# tappytap.net
KiCad netlist of a schematic drawn in EAGLE
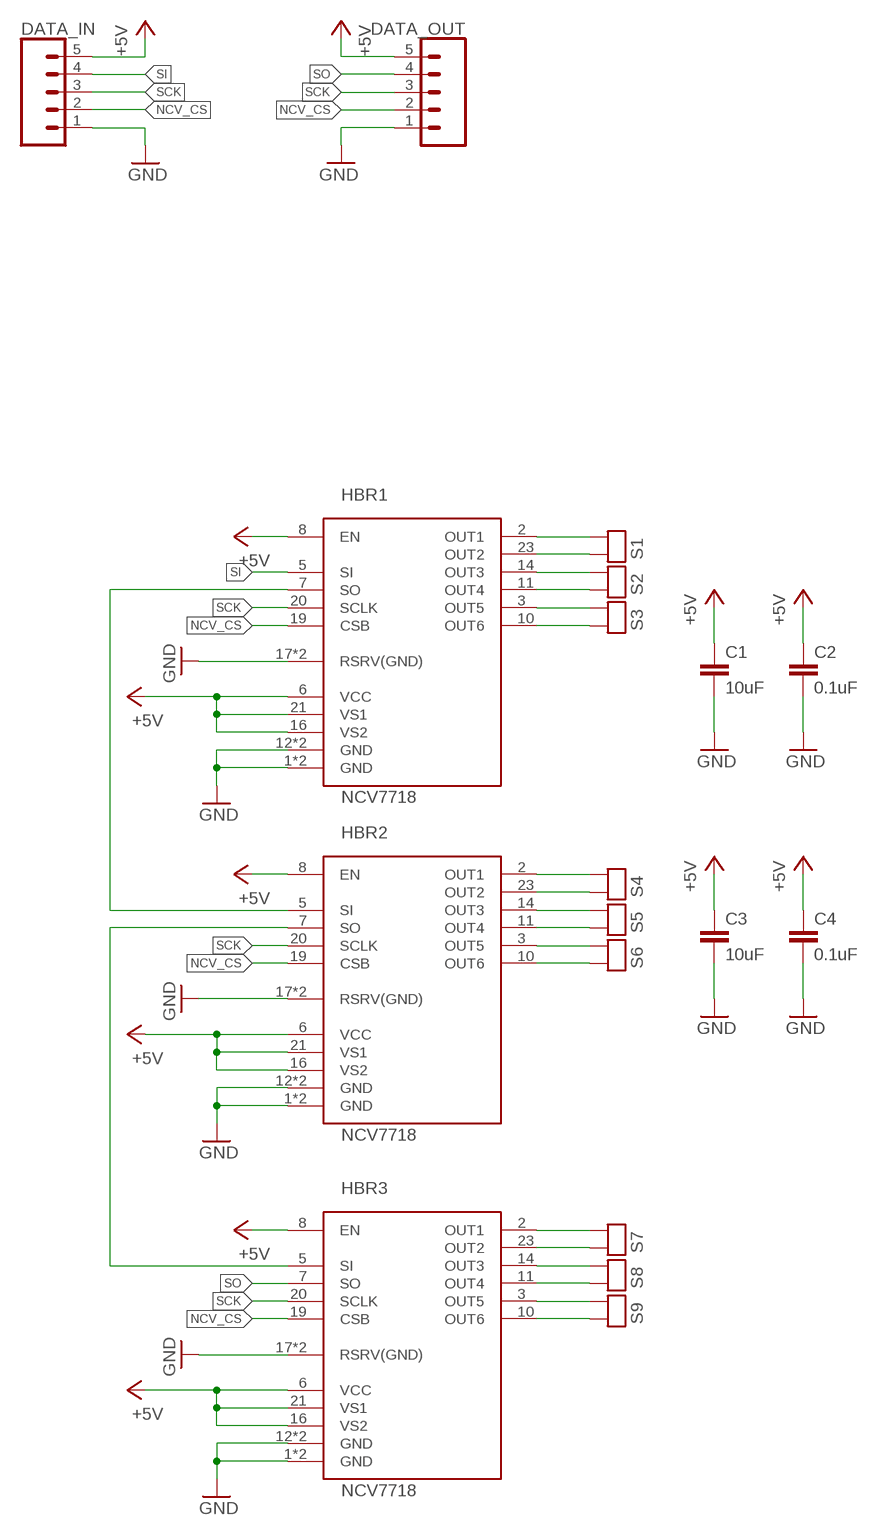
[diagram p0: schematic, sheet 1]

(export (version "E")
  (design (tool "Eeschema 10.0.6"))
  (components
    (comp (ref "C1")
      (value "10uF")
      (footprint "eagle-import:C0603")
      (libsource (lib "eagle-import") (part "C-EUC0603"))
    )
    (comp (ref "C2")
      (value "0.1uF")
      (footprint "eagle-import:C0603")
      (libsource (lib "eagle-import") (part "C-EUC0603"))
    )
    (comp (ref "C3")
      (value "10uF")
      (footprint "eagle-import:C0603")
      (libsource (lib "eagle-import") (part "C-EUC0603"))
    )
    (comp (ref "C4")
      (value "0.1uF")
      (footprint "eagle-import:C0603")
      (libsource (lib "eagle-import") (part "C-EUC0603"))
    )
    (comp (ref "DATA_IN")
      (value "CONN_05")
      (footprint "eagle-import:1X05")
      (libsource (lib "eagle-import") (part "CONN_05"))
    )
    (comp (ref "DATA_OUT")
      (value "CONN_05")
      (footprint "eagle-import:1X05")
      (libsource (lib "eagle-import") (part "CONN_05"))
    )
    (comp (ref "HBR1")
      (value "NCV7718")
      (footprint "eagle-import:24-SSOP")
      (libsource (lib "eagle-import") (part "NCV7718"))
    )
    (comp (ref "HBR2")
      (value "NCV7718")
      (footprint "eagle-import:24-SSOP")
      (libsource (lib "eagle-import") (part "NCV7718"))
    )
    (comp (ref "HBR3")
      (value "NCV7718")
      (footprint "eagle-import:24-SSOP")
      (libsource (lib "eagle-import") (part "NCV7718"))
    )
    (comp (ref "S1")
      (value "TP2")
      (footprint "eagle-import:TP2_2MM")
      (libsource (lib "eagle-import") (part "TP2"))
    )
    (comp (ref "S2")
      (value "TP2")
      (footprint "eagle-import:TP2_2MM")
      (libsource (lib "eagle-import") (part "TP2"))
    )
    (comp (ref "S3")
      (value "TP2")
      (footprint "eagle-import:TP2_2MM")
      (libsource (lib "eagle-import") (part "TP2"))
    )
    (comp (ref "S4")
      (value "TP2")
      (footprint "eagle-import:TP2_2MM")
      (libsource (lib "eagle-import") (part "TP2"))
    )
    (comp (ref "S5")
      (value "TP2")
      (footprint "eagle-import:TP2_2MM")
      (libsource (lib "eagle-import") (part "TP2"))
    )
    (comp (ref "S6")
      (value "TP2")
      (footprint "eagle-import:TP2_2MM")
      (libsource (lib "eagle-import") (part "TP2"))
    )
    (comp (ref "S7")
      (value "TP2")
      (footprint "eagle-import:TP2_2MM")
      (libsource (lib "eagle-import") (part "TP2"))
    )
    (comp (ref "S8")
      (value "TP2")
      (footprint "eagle-import:TP2_2MM")
      (libsource (lib "eagle-import") (part "TP2"))
    )
    (comp (ref "S9")
      (value "TP2")
      (footprint "eagle-import:TP2_2MM")
      (libsource (lib "eagle-import") (part "TP2"))
    )
  )
  (nets
    (net (code "1") (name "+5V") (class "Default")
      (node (ref "C1") (pin "1") (pinfunction "1_1") (pintype "passive"))
      (node (ref "C2") (pin "1") (pinfunction "1_1") (pintype "passive"))
      (node (ref "C3") (pin "1") (pinfunction "1_1") (pintype "passive"))
      (node (ref "C4") (pin "1") (pinfunction "1_1") (pintype "passive"))
      (node (ref "DATA_IN") (pin "5") (pinfunction "5_5") (pintype "passive"))
      (node (ref "DATA_OUT") (pin "5") (pinfunction "5_5") (pintype "passive"))
      (node (ref "HBR1") (pin "16") (pinfunction "VS2_16") (pintype "bidirectional"))
      (node (ref "HBR1") (pin "21") (pinfunction "VS1_21") (pintype "bidirectional"))
      (node (ref "HBR1") (pin "6") (pinfunction "VCC_6") (pintype "bidirectional"))
      (node (ref "HBR1") (pin "8") (pinfunction "EN_8") (pintype "bidirectional"))
      (node (ref "HBR2") (pin "16") (pinfunction "VS2_16") (pintype "bidirectional"))
      (node (ref "HBR2") (pin "21") (pinfunction "VS1_21") (pintype "bidirectional"))
      (node (ref "HBR2") (pin "6") (pinfunction "VCC_6") (pintype "bidirectional"))
      (node (ref "HBR2") (pin "8") (pinfunction "EN_8") (pintype "bidirectional"))
      (node (ref "HBR3") (pin "16") (pinfunction "VS2_16") (pintype "bidirectional"))
      (node (ref "HBR3") (pin "21") (pinfunction "VS1_21") (pintype "bidirectional"))
      (node (ref "HBR3") (pin "6") (pinfunction "VCC_6") (pintype "bidirectional"))
      (node (ref "HBR3") (pin "8") (pinfunction "EN_8") (pintype "bidirectional"))
    )
    (net (code "2") (name "GND") (class "Default")
      (node (ref "C1") (pin "2") (pinfunction "2_2") (pintype "passive"))
      (node (ref "C2") (pin "2") (pinfunction "2_2") (pintype "passive"))
      (node (ref "C3") (pin "2") (pinfunction "2_2") (pintype "passive"))
      (node (ref "C4") (pin "2") (pinfunction "2_2") (pintype "passive"))
      (node (ref "DATA_IN") (pin "1") (pinfunction "1_1") (pintype "passive"))
      (node (ref "DATA_OUT") (pin "1") (pinfunction "1_1") (pintype "passive"))
      (node (ref "HBR1") (pin "1") (pinfunction "GND_1") (pintype "bidirectional"))
      (node (ref "HBR1") (pin "12") (pinfunction "GND_12") (pintype "bidirectional"))
      (node (ref "HBR1") (pin "13") (pinfunction "GND_13") (pintype "bidirectional"))
      (node (ref "HBR1") (pin "17") (pinfunction "RSRV(GND)_17") (pintype "bidirectional"))
      (node (ref "HBR1") (pin "18") (pinfunction "RSRV(GND)_18") (pintype "bidirectional"))
      (node (ref "HBR1") (pin "24") (pinfunction "GND_24") (pintype "bidirectional"))
      (node (ref "HBR2") (pin "1") (pinfunction "GND_1") (pintype "bidirectional"))
      (node (ref "HBR2") (pin "12") (pinfunction "GND_12") (pintype "bidirectional"))
      (node (ref "HBR2") (pin "13") (pinfunction "GND_13") (pintype "bidirectional"))
      (node (ref "HBR2") (pin "17") (pinfunction "RSRV(GND)_17") (pintype "bidirectional"))
      (node (ref "HBR2") (pin "18") (pinfunction "RSRV(GND)_18") (pintype "bidirectional"))
      (node (ref "HBR2") (pin "24") (pinfunction "GND_24") (pintype "bidirectional"))
      (node (ref "HBR3") (pin "1") (pinfunction "GND_1") (pintype "bidirectional"))
      (node (ref "HBR3") (pin "12") (pinfunction "GND_12") (pintype "bidirectional"))
      (node (ref "HBR3") (pin "13") (pinfunction "GND_13") (pintype "bidirectional"))
      (node (ref "HBR3") (pin "17") (pinfunction "RSRV(GND)_17") (pintype "bidirectional"))
      (node (ref "HBR3") (pin "18") (pinfunction "RSRV(GND)_18") (pintype "bidirectional"))
      (node (ref "HBR3") (pin "24") (pinfunction "GND_24") (pintype "bidirectional"))
    )
    (net (code "3") (name "NCV_CS") (class "Default")
      (node (ref "DATA_IN") (pin "2") (pinfunction "2_2") (pintype "passive"))
      (node (ref "DATA_OUT") (pin "2") (pinfunction "2_2") (pintype "passive"))
      (node (ref "HBR1") (pin "19") (pinfunction "CSB_19") (pintype "bidirectional"))
      (node (ref "HBR2") (pin "19") (pinfunction "CSB_19") (pintype "bidirectional"))
      (node (ref "HBR3") (pin "19") (pinfunction "CSB_19") (pintype "bidirectional"))
    )
    (net (code "4") (name "Net-(HBR1-OUT1)") (class "Default")
      (node (ref "HBR1") (pin "2") (pinfunction "OUT1_2") (pintype "bidirectional"))
      (node (ref "S1") (pin "P$1") (pinfunction "0_P$1") (pintype "bidirectional"))
    )
    (net (code "5") (name "Net-(HBR1-OUT2)") (class "Default")
      (node (ref "HBR1") (pin "23") (pinfunction "OUT2_23") (pintype "bidirectional"))
      (node (ref "S1") (pin "P$2") (pinfunction "1_P$2") (pintype "bidirectional"))
    )
    (net (code "6") (name "Net-(HBR1-OUT3)") (class "Default")
      (node (ref "HBR1") (pin "14") (pinfunction "OUT3_14") (pintype "bidirectional"))
      (node (ref "S2") (pin "P$1") (pinfunction "0_P$1") (pintype "bidirectional"))
    )
    (net (code "7") (name "Net-(HBR1-OUT4)") (class "Default")
      (node (ref "HBR1") (pin "11") (pinfunction "OUT4_11") (pintype "bidirectional"))
      (node (ref "S2") (pin "P$2") (pinfunction "1_P$2") (pintype "bidirectional"))
    )
    (net (code "8") (name "Net-(HBR1-OUT5)") (class "Default")
      (node (ref "HBR1") (pin "3") (pinfunction "OUT5_3") (pintype "bidirectional"))
      (node (ref "S3") (pin "P$1") (pinfunction "0_P$1") (pintype "bidirectional"))
    )
    (net (code "9") (name "Net-(HBR1-OUT6)") (class "Default")
      (node (ref "HBR1") (pin "10") (pinfunction "OUT6_10") (pintype "bidirectional"))
      (node (ref "S3") (pin "P$2") (pinfunction "1_P$2") (pintype "bidirectional"))
    )
    (net (code "10") (name "Net-(HBR1-SO)") (class "Default")
      (node (ref "HBR1") (pin "7") (pinfunction "SO_7") (pintype "bidirectional"))
      (node (ref "HBR2") (pin "5") (pinfunction "SI_5") (pintype "bidirectional"))
    )
    (net (code "11") (name "Net-(HBR2-OUT1)") (class "Default")
      (node (ref "HBR2") (pin "2") (pinfunction "OUT1_2") (pintype "bidirectional"))
      (node (ref "S4") (pin "P$1") (pinfunction "0_P$1") (pintype "bidirectional"))
    )
    (net (code "12") (name "Net-(HBR2-OUT2)") (class "Default")
      (node (ref "HBR2") (pin "23") (pinfunction "OUT2_23") (pintype "bidirectional"))
      (node (ref "S4") (pin "P$2") (pinfunction "1_P$2") (pintype "bidirectional"))
    )
    (net (code "13") (name "Net-(HBR2-OUT3)") (class "Default")
      (node (ref "HBR2") (pin "14") (pinfunction "OUT3_14") (pintype "bidirectional"))
      (node (ref "S5") (pin "P$1") (pinfunction "0_P$1") (pintype "bidirectional"))
    )
    (net (code "14") (name "Net-(HBR2-OUT4)") (class "Default")
      (node (ref "HBR2") (pin "11") (pinfunction "OUT4_11") (pintype "bidirectional"))
      (node (ref "S5") (pin "P$2") (pinfunction "1_P$2") (pintype "bidirectional"))
    )
    (net (code "15") (name "Net-(HBR2-OUT5)") (class "Default")
      (node (ref "HBR2") (pin "3") (pinfunction "OUT5_3") (pintype "bidirectional"))
      (node (ref "S6") (pin "P$1") (pinfunction "0_P$1") (pintype "bidirectional"))
    )
    (net (code "16") (name "Net-(HBR2-OUT6)") (class "Default")
      (node (ref "HBR2") (pin "10") (pinfunction "OUT6_10") (pintype "bidirectional"))
      (node (ref "S6") (pin "P$2") (pinfunction "1_P$2") (pintype "bidirectional"))
    )
    (net (code "17") (name "Net-(HBR2-SO)") (class "Default")
      (node (ref "HBR2") (pin "7") (pinfunction "SO_7") (pintype "bidirectional"))
      (node (ref "HBR3") (pin "5") (pinfunction "SI_5") (pintype "bidirectional"))
    )
    (net (code "18") (name "Net-(HBR3-OUT1)") (class "Default")
      (node (ref "HBR3") (pin "2") (pinfunction "OUT1_2") (pintype "bidirectional"))
      (node (ref "S7") (pin "P$1") (pinfunction "0_P$1") (pintype "bidirectional"))
    )
    (net (code "19") (name "Net-(HBR3-OUT2)") (class "Default")
      (node (ref "HBR3") (pin "23") (pinfunction "OUT2_23") (pintype "bidirectional"))
      (node (ref "S7") (pin "P$2") (pinfunction "1_P$2") (pintype "bidirectional"))
    )
    (net (code "20") (name "Net-(HBR3-OUT3)") (class "Default")
      (node (ref "HBR3") (pin "14") (pinfunction "OUT3_14") (pintype "bidirectional"))
      (node (ref "S8") (pin "P$1") (pinfunction "0_P$1") (pintype "bidirectional"))
    )
    (net (code "21") (name "Net-(HBR3-OUT4)") (class "Default")
      (node (ref "HBR3") (pin "11") (pinfunction "OUT4_11") (pintype "bidirectional"))
      (node (ref "S8") (pin "P$2") (pinfunction "1_P$2") (pintype "bidirectional"))
    )
    (net (code "22") (name "Net-(HBR3-OUT5)") (class "Default")
      (node (ref "HBR3") (pin "3") (pinfunction "OUT5_3") (pintype "bidirectional"))
      (node (ref "S9") (pin "P$1") (pinfunction "0_P$1") (pintype "bidirectional"))
    )
    (net (code "23") (name "Net-(HBR3-OUT6)") (class "Default")
      (node (ref "HBR3") (pin "10") (pinfunction "OUT6_10") (pintype "bidirectional"))
      (node (ref "S9") (pin "P$2") (pinfunction "1_P$2") (pintype "bidirectional"))
    )
    (net (code "24") (name "SCK") (class "Default")
      (node (ref "DATA_IN") (pin "3") (pinfunction "3_3") (pintype "passive"))
      (node (ref "DATA_OUT") (pin "3") (pinfunction "3_3") (pintype "passive"))
      (node (ref "HBR1") (pin "20") (pinfunction "SCLK_20") (pintype "bidirectional"))
      (node (ref "HBR2") (pin "20") (pinfunction "SCLK_20") (pintype "bidirectional"))
      (node (ref "HBR3") (pin "20") (pinfunction "SCLK_20") (pintype "bidirectional"))
    )
    (net (code "25") (name "SI") (class "Default")
      (node (ref "DATA_IN") (pin "4") (pinfunction "4_4") (pintype "passive"))
      (node (ref "HBR1") (pin "5") (pinfunction "SI_5") (pintype "bidirectional"))
    )
    (net (code "26") (name "SO") (class "Default")
      (node (ref "DATA_OUT") (pin "4") (pinfunction "4_4") (pintype "passive"))
      (node (ref "HBR3") (pin "7") (pinfunction "SO_7") (pintype "bidirectional"))
    )
  )
)
